# untitledfonte2.net
KiCad netlist of a schematic drawn in EAGLE
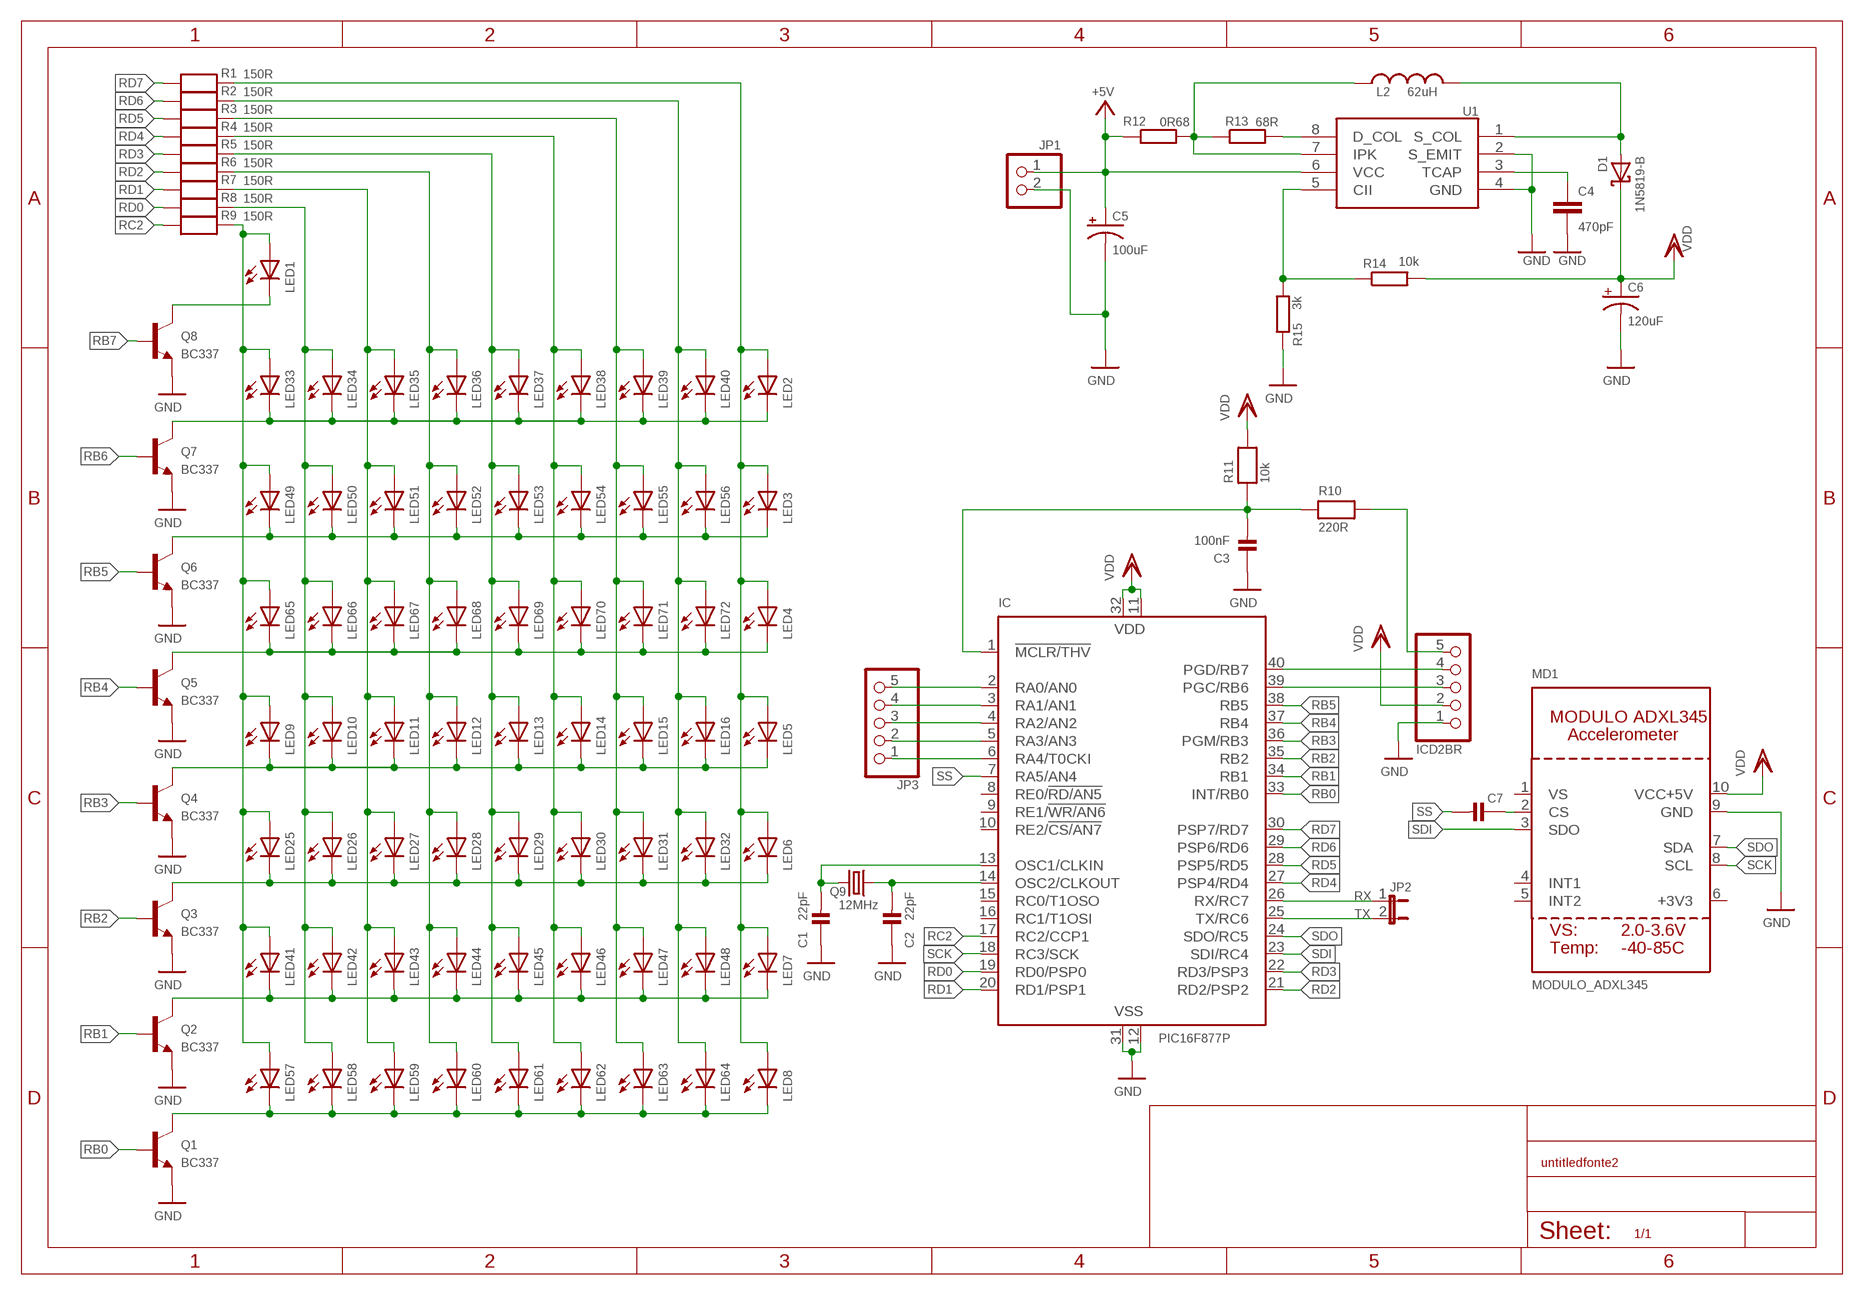
[diagram p0: schematic, sheet 1]

(export (version "E")
  (design (tool "Eeschema 10.0.6"))
  (components
    (comp (ref "C1")
      (value "22pF")
      (footprint "eagle-import:0805_NOTHERMALS")
      (libsource (lib "eagle-import") (part "CAP_CERAMIC0805-NOTHERMALS"))
    )
    (comp (ref "C2")
      (value "22pF")
      (footprint "eagle-import:0805_NOTHERMALS")
      (libsource (lib "eagle-import") (part "CAP_CERAMIC0805-NOTHERMALS"))
    )
    (comp (ref "C3")
      (value "100nF")
      (footprint "eagle-import:0805_NOTHERMALS")
      (libsource (lib "eagle-import") (part "CAP_CERAMIC0805-NOTHERMALS"))
    )
    (comp (ref "C4")
      (value "470pF")
      (footprint "eagle-import:C0805")
      (libsource (lib "eagle-import") (part "C-EUC0805"))
    )
    (comp (ref "C5")
      (value "100uF")
      (footprint "eagle-import:E2,5-5")
      (libsource (lib "eagle-import") (part "CPOL-USE2.5-5"))
    )
    (comp (ref "C6")
      (value "120uF")
      (footprint "eagle-import:E2,5-5")
      (libsource (lib "eagle-import") (part "CPOL-USE2.5-5"))
    )
    (comp (ref "C7")
      (value "CAP_CERAMIC0805-NOTHERMALS")
      (footprint "eagle-import:0805_NOTHERMALS")
      (libsource (lib "eagle-import") (part "CAP_CERAMIC0805-NOTHERMALS"))
    )
    (comp (ref "D1")
      (value "1N5819-B")
      (footprint "eagle-import:DO41-7.6")
      (libsource (lib "eagle-import") (part "1N5819-B"))
    )
    (comp (ref "IC")
      (value "PIC16F877P")
      (footprint "eagle-import:DIL40")
      (fields (field (name "MF") "MICROCHIP") (field (name "MPN") "PIC16F877-04/P"))
      (libsource (lib "eagle-import") (part "PIC16F87P7"))
    )
    (comp (ref "ICD2BR")
      (value "HEADER-1X5ROUND")
      (footprint "eagle-import:1X05_ROUND")
      (libsource (lib "eagle-import") (part "HEADER-1X5ROUND"))
    )
    (comp (ref "JP1")
      (value "HEADER-1X2")
      (footprint "eagle-import:1X02_OVAL")
      (libsource (lib "eagle-import") (part "HEADER-1X2"))
    )
    (comp (ref "JP2")
      (value "JUMPER2")
      (footprint "eagle-import:JUMPER2")
      (libsource (lib "eagle-import") (part "JUMPER2"))
    )
    (comp (ref "JP3")
      (value "HEADER-1X5ROUND")
      (footprint "eagle-import:1X05_ROUND")
      (libsource (lib "eagle-import") (part "HEADER-1X5ROUND"))
    )
    (comp (ref "L2")
      (value "62uH")
      (footprint "eagle-import:0204_5")
      (libsource (lib "eagle-import") (part "L-US0204/5"))
    )
    (comp (ref "LED1")
      (value "LED3MM")
      (footprint "eagle-import:LED3MM")
      (libsource (lib "eagle-import") (part "LED3MM"))
    )
    (comp (ref "LED2")
      (value "LED3MM")
      (footprint "eagle-import:LED3MM")
      (libsource (lib "eagle-import") (part "LED3MM"))
    )
    (comp (ref "LED3")
      (value "LED3MM")
      (footprint "eagle-import:LED3MM")
      (libsource (lib "eagle-import") (part "LED3MM"))
    )
    (comp (ref "LED4")
      (value "LED3MM")
      (footprint "eagle-import:LED3MM")
      (libsource (lib "eagle-import") (part "LED3MM"))
    )
    (comp (ref "LED5")
      (value "LED3MM")
      (footprint "eagle-import:LED3MM")
      (libsource (lib "eagle-import") (part "LED3MM"))
    )
    (comp (ref "LED6")
      (value "LED3MM")
      (footprint "eagle-import:LED3MM")
      (libsource (lib "eagle-import") (part "LED3MM"))
    )
    (comp (ref "LED7")
      (value "LED3MM")
      (footprint "eagle-import:LED3MM")
      (libsource (lib "eagle-import") (part "LED3MM"))
    )
    (comp (ref "LED8")
      (value "LED3MM")
      (footprint "eagle-import:LED3MM")
      (libsource (lib "eagle-import") (part "LED3MM"))
    )
    (comp (ref "LED9")
      (value "LED3MM")
      (footprint "eagle-import:LED3MM")
      (libsource (lib "eagle-import") (part "LED3MM"))
    )
    (comp (ref "LED10")
      (value "LED3MM")
      (footprint "eagle-import:LED3MM")
      (libsource (lib "eagle-import") (part "LED3MM"))
    )
    (comp (ref "LED11")
      (value "LED3MM")
      (footprint "eagle-import:LED3MM")
      (libsource (lib "eagle-import") (part "LED3MM"))
    )
    (comp (ref "LED12")
      (value "LED3MM")
      (footprint "eagle-import:LED3MM")
      (libsource (lib "eagle-import") (part "LED3MM"))
    )
    (comp (ref "LED13")
      (value "LED3MM")
      (footprint "eagle-import:LED3MM")
      (libsource (lib "eagle-import") (part "LED3MM"))
    )
    (comp (ref "LED14")
      (value "LED3MM")
      (footprint "eagle-import:LED3MM")
      (libsource (lib "eagle-import") (part "LED3MM"))
    )
    (comp (ref "LED15")
      (value "LED3MM")
      (footprint "eagle-import:LED3MM")
      (libsource (lib "eagle-import") (part "LED3MM"))
    )
    (comp (ref "LED16")
      (value "LED3MM")
      (footprint "eagle-import:LED3MM")
      (libsource (lib "eagle-import") (part "LED3MM"))
    )
    (comp (ref "LED25")
      (value "LED3MM")
      (footprint "eagle-import:LED3MM")
      (libsource (lib "eagle-import") (part "LED3MM"))
    )
    (comp (ref "LED26")
      (value "LED3MM")
      (footprint "eagle-import:LED3MM")
      (libsource (lib "eagle-import") (part "LED3MM"))
    )
    (comp (ref "LED27")
      (value "LED3MM")
      (footprint "eagle-import:LED3MM")
      (libsource (lib "eagle-import") (part "LED3MM"))
    )
    (comp (ref "LED28")
      (value "LED3MM")
      (footprint "eagle-import:LED3MM")
      (libsource (lib "eagle-import") (part "LED3MM"))
    )
    (comp (ref "LED29")
      (value "LED3MM")
      (footprint "eagle-import:LED3MM")
      (libsource (lib "eagle-import") (part "LED3MM"))
    )
    (comp (ref "LED30")
      (value "LED3MM")
      (footprint "eagle-import:LED3MM")
      (libsource (lib "eagle-import") (part "LED3MM"))
    )
    (comp (ref "LED31")
      (value "LED3MM")
      (footprint "eagle-import:LED3MM")
      (libsource (lib "eagle-import") (part "LED3MM"))
    )
    (comp (ref "LED32")
      (value "LED3MM")
      (footprint "eagle-import:LED3MM")
      (libsource (lib "eagle-import") (part "LED3MM"))
    )
    (comp (ref "LED33")
      (value "LED3MM")
      (footprint "eagle-import:LED3MM")
      (libsource (lib "eagle-import") (part "LED3MM"))
    )
    (comp (ref "LED34")
      (value "LED3MM")
      (footprint "eagle-import:LED3MM")
      (libsource (lib "eagle-import") (part "LED3MM"))
    )
    (comp (ref "LED35")
      (value "LED3MM")
      (footprint "eagle-import:LED3MM")
      (libsource (lib "eagle-import") (part "LED3MM"))
    )
    (comp (ref "LED36")
      (value "LED3MM")
      (footprint "eagle-import:LED3MM")
      (libsource (lib "eagle-import") (part "LED3MM"))
    )
    (comp (ref "LED37")
      (value "LED3MM")
      (footprint "eagle-import:LED3MM")
      (libsource (lib "eagle-import") (part "LED3MM"))
    )
    (comp (ref "LED38")
      (value "LED3MM")
      (footprint "eagle-import:LED3MM")
      (libsource (lib "eagle-import") (part "LED3MM"))
    )
    (comp (ref "LED39")
      (value "LED3MM")
      (footprint "eagle-import:LED3MM")
      (libsource (lib "eagle-import") (part "LED3MM"))
    )
    (comp (ref "LED40")
      (value "LED3MM")
      (footprint "eagle-import:LED3MM")
      (libsource (lib "eagle-import") (part "LED3MM"))
    )
    (comp (ref "LED41")
      (value "LED3MM")
      (footprint "eagle-import:LED3MM")
      (libsource (lib "eagle-import") (part "LED3MM"))
    )
    (comp (ref "LED42")
      (value "LED3MM")
      (footprint "eagle-import:LED3MM")
      (libsource (lib "eagle-import") (part "LED3MM"))
    )
    (comp (ref "LED43")
      (value "LED3MM")
      (footprint "eagle-import:LED3MM")
      (libsource (lib "eagle-import") (part "LED3MM"))
    )
    (comp (ref "LED44")
      (value "LED3MM")
      (footprint "eagle-import:LED3MM")
      (libsource (lib "eagle-import") (part "LED3MM"))
    )
    (comp (ref "LED45")
      (value "LED3MM")
      (footprint "eagle-import:LED3MM")
      (libsource (lib "eagle-import") (part "LED3MM"))
    )
    (comp (ref "LED46")
      (value "LED3MM")
      (footprint "eagle-import:LED3MM")
      (libsource (lib "eagle-import") (part "LED3MM"))
    )
    (comp (ref "LED47")
      (value "LED3MM")
      (footprint "eagle-import:LED3MM")
      (libsource (lib "eagle-import") (part "LED3MM"))
    )
    (comp (ref "LED48")
      (value "LED3MM")
      (footprint "eagle-import:LED3MM")
      (libsource (lib "eagle-import") (part "LED3MM"))
    )
    (comp (ref "LED49")
      (value "LED3MM")
      (footprint "eagle-import:LED3MM")
      (libsource (lib "eagle-import") (part "LED3MM"))
    )
    (comp (ref "LED50")
      (value "LED3MM")
      (footprint "eagle-import:LED3MM")
      (libsource (lib "eagle-import") (part "LED3MM"))
    )
    (comp (ref "LED51")
      (value "LED3MM")
      (footprint "eagle-import:LED3MM")
      (libsource (lib "eagle-import") (part "LED3MM"))
    )
    (comp (ref "LED52")
      (value "LED3MM")
      (footprint "eagle-import:LED3MM")
      (libsource (lib "eagle-import") (part "LED3MM"))
    )
    (comp (ref "LED53")
      (value "LED3MM")
      (footprint "eagle-import:LED3MM")
      (libsource (lib "eagle-import") (part "LED3MM"))
    )
    (comp (ref "LED54")
      (value "LED3MM")
      (footprint "eagle-import:LED3MM")
      (libsource (lib "eagle-import") (part "LED3MM"))
    )
    (comp (ref "LED55")
      (value "LED3MM")
      (footprint "eagle-import:LED3MM")
      (libsource (lib "eagle-import") (part "LED3MM"))
    )
    (comp (ref "LED56")
      (value "LED3MM")
      (footprint "eagle-import:LED3MM")
      (libsource (lib "eagle-import") (part "LED3MM"))
    )
    (comp (ref "LED57")
      (value "LED3MM")
      (footprint "eagle-import:LED3MM")
      (libsource (lib "eagle-import") (part "LED3MM"))
    )
    (comp (ref "LED58")
      (value "LED3MM")
      (footprint "eagle-import:LED3MM")
      (libsource (lib "eagle-import") (part "LED3MM"))
    )
    (comp (ref "LED59")
      (value "LED3MM")
      (footprint "eagle-import:LED3MM")
      (libsource (lib "eagle-import") (part "LED3MM"))
    )
    (comp (ref "LED60")
      (value "LED3MM")
      (footprint "eagle-import:LED3MM")
      (libsource (lib "eagle-import") (part "LED3MM"))
    )
    (comp (ref "LED61")
      (value "LED3MM")
      (footprint "eagle-import:LED3MM")
      (libsource (lib "eagle-import") (part "LED3MM"))
    )
    (comp (ref "LED62")
      (value "LED3MM")
      (footprint "eagle-import:LED3MM")
      (libsource (lib "eagle-import") (part "LED3MM"))
    )
    (comp (ref "LED63")
      (value "LED3MM")
      (footprint "eagle-import:LED3MM")
      (libsource (lib "eagle-import") (part "LED3MM"))
    )
    (comp (ref "LED64")
      (value "LED3MM")
      (footprint "eagle-import:LED3MM")
      (libsource (lib "eagle-import") (part "LED3MM"))
    )
    (comp (ref "LED65")
      (value "LED3MM")
      (footprint "eagle-import:LED3MM")
      (libsource (lib "eagle-import") (part "LED3MM"))
    )
    (comp (ref "LED66")
      (value "LED3MM")
      (footprint "eagle-import:LED3MM")
      (libsource (lib "eagle-import") (part "LED3MM"))
    )
    (comp (ref "LED67")
      (value "LED3MM")
      (footprint "eagle-import:LED3MM")
      (libsource (lib "eagle-import") (part "LED3MM"))
    )
    (comp (ref "LED68")
      (value "LED3MM")
      (footprint "eagle-import:LED3MM")
      (libsource (lib "eagle-import") (part "LED3MM"))
    )
    (comp (ref "LED69")
      (value "LED3MM")
      (footprint "eagle-import:LED3MM")
      (libsource (lib "eagle-import") (part "LED3MM"))
    )
    (comp (ref "LED70")
      (value "LED3MM")
      (footprint "eagle-import:LED3MM")
      (libsource (lib "eagle-import") (part "LED3MM"))
    )
    (comp (ref "LED71")
      (value "LED3MM")
      (footprint "eagle-import:LED3MM")
      (libsource (lib "eagle-import") (part "LED3MM"))
    )
    (comp (ref "LED72")
      (value "LED3MM")
      (footprint "eagle-import:LED3MM")
      (libsource (lib "eagle-import") (part "LED3MM"))
    )
    (comp (ref "MD1")
      (value "MODULO_ADXL345")
      (footprint "eagle-import:MODULO_ADXL345")
      (libsource (lib "eagle-import") (part "MODULO_ADXL345"))
    )
    (comp (ref "Q1")
      (value "BC337")
      (footprint "eagle-import:TO92")
      (libsource (lib "eagle-import") (part "BC337"))
    )
    (comp (ref "Q2")
      (value "BC337")
      (footprint "eagle-import:TO92")
      (libsource (lib "eagle-import") (part "BC337"))
    )
    (comp (ref "Q3")
      (value "BC337")
      (footprint "eagle-import:TO92")
      (libsource (lib "eagle-import") (part "BC337"))
    )
    (comp (ref "Q4")
      (value "BC337")
      (footprint "eagle-import:TO92")
      (libsource (lib "eagle-import") (part "BC337"))
    )
    (comp (ref "Q5")
      (value "BC337")
      (footprint "eagle-import:TO92")
      (libsource (lib "eagle-import") (part "BC337"))
    )
    (comp (ref "Q6")
      (value "BC337")
      (footprint "eagle-import:TO92")
      (libsource (lib "eagle-import") (part "BC337"))
    )
    (comp (ref "Q7")
      (value "BC337")
      (footprint "eagle-import:TO92")
      (libsource (lib "eagle-import") (part "BC337"))
    )
    (comp (ref "Q8")
      (value "BC337")
      (footprint "eagle-import:TO92")
      (libsource (lib "eagle-import") (part "BC337"))
    )
    (comp (ref "Q9")
      (value "12MHz")
      (footprint "eagle-import:HC49_S")
      (libsource (lib "eagle-import") (part "CRYSTALHC49S"))
    )
    (comp (ref "R1")
      (value "150R")
      (footprint "eagle-import:0805_NOTHERMALS")
      (libsource (lib "eagle-import") (part "RESISTOR0805_NOTHERMALS"))
    )
    (comp (ref "R2")
      (value "150R")
      (footprint "eagle-import:0805_NOTHERMALS")
      (libsource (lib "eagle-import") (part "RESISTOR0805_NOTHERMALS"))
    )
    (comp (ref "R3")
      (value "150R")
      (footprint "eagle-import:0805_NOTHERMALS")
      (libsource (lib "eagle-import") (part "RESISTOR0805_NOTHERMALS"))
    )
    (comp (ref "R4")
      (value "150R")
      (footprint "eagle-import:0805_NOTHERMALS")
      (libsource (lib "eagle-import") (part "RESISTOR0805_NOTHERMALS"))
    )
    (comp (ref "R5")
      (value "150R")
      (footprint "eagle-import:0805_NOTHERMALS")
      (libsource (lib "eagle-import") (part "RESISTOR0805_NOTHERMALS"))
    )
    (comp (ref "R6")
      (value "150R")
      (footprint "eagle-import:0805_NOTHERMALS")
      (libsource (lib "eagle-import") (part "RESISTOR0805_NOTHERMALS"))
    )
    (comp (ref "R7")
      (value "150R")
      (footprint "eagle-import:0805_NOTHERMALS")
      (libsource (lib "eagle-import") (part "RESISTOR0805_NOTHERMALS"))
    )
    (comp (ref "R8")
      (value "150R")
      (footprint "eagle-import:0805_NOTHERMALS")
      (libsource (lib "eagle-import") (part "RESISTOR0805_NOTHERMALS"))
    )
    (comp (ref "R9")
      (value "150R")
      (footprint "eagle-import:0805_NOTHERMALS")
      (libsource (lib "eagle-import") (part "RESISTOR0805_NOTHERMALS"))
    )
    (comp (ref "R10")
      (value "220R")
      (footprint "eagle-import:0805_NOTHERMALS")
      (libsource (lib "eagle-import") (part "RESISTOR0805_NOTHERMALS"))
    )
    (comp (ref "R11")
      (value "10k")
      (footprint "eagle-import:0805_NOTHERMALS")
      (libsource (lib "eagle-import") (part "RESISTOR0805_NOTHERMALS"))
    )
    (comp (ref "R12")
      (value "0R68")
      (footprint "eagle-import:0207_5V")
      (libsource (lib "eagle-import") (part "R-EU_0207/5V"))
    )
    (comp (ref "R13")
      (value "68R")
      (footprint "eagle-import:0207_2V")
      (libsource (lib "eagle-import") (part "R-EU_0207/2V"))
    )
    (comp (ref "R14")
      (value "10k")
      (footprint "eagle-import:0207_2V")
      (libsource (lib "eagle-import") (part "R-EU_0207/2V"))
    )
    (comp (ref "R15")
      (value "3k")
      (footprint "eagle-import:0207_2V")
      (libsource (lib "eagle-import") (part "R-EU_0207/2V"))
    )
    (comp (ref "U1")
      (value "MC34063A")
      (footprint "eagle-import:SOIC8_150MIL")
      (libsource (lib "eagle-import") (part "MC34063A"))
    )
  )
  (nets
    (net (code "1") (name "+5V") (class "Default")
      (node (ref "C5") (pin "+") (pinfunction "+_+") (pintype "passive"))
      (node (ref "JP1") (pin "1") (pinfunction "1_1") (pintype "passive"))
      (node (ref "R12") (pin "1") (pinfunction "1_1") (pintype "passive"))
      (node (ref "U1") (pin "6") (pinfunction "VCC_6") (pintype "bidirectional"))
    )
    (net (code "2") (name "/RX") (class "Default")
      (node (ref "IC") (pin "26") (pinfunction "RX/RC7_26") (pintype "bidirectional"))
      (node (ref "JP2") (pin "1") (pinfunction "1_1") (pintype "passive"))
    )
    (net (code "3") (name "/TX") (class "Default")
      (node (ref "IC") (pin "25") (pinfunction "TX/RC6_25") (pintype "bidirectional"))
      (node (ref "JP2") (pin "2") (pinfunction "2_2") (pintype "passive"))
    )
    (net (code "4") (name "GND") (class "Default")
      (node (ref "C1") (pin "1") (pinfunction "P$1_1") (pintype "passive"))
      (node (ref "C2") (pin "1") (pinfunction "P$1_1") (pintype "passive"))
      (node (ref "C3") (pin "1") (pinfunction "P$1_1") (pintype "passive"))
      (node (ref "C4") (pin "2") (pinfunction "2_2") (pintype "passive"))
      (node (ref "C5") (pin "-") (pinfunction "-_-") (pintype "passive"))
      (node (ref "C6") (pin "-") (pinfunction "-_-") (pintype "passive"))
      (node (ref "IC") (pin "12") (pinfunction "VSS_12") (pintype "power_in"))
      (node (ref "IC") (pin "31") (pinfunction "VSS_31") (pintype "power_in"))
      (node (ref "ICD2BR") (pin "1") (pinfunction "1_1") (pintype "passive"))
      (node (ref "JP1") (pin "2") (pinfunction "2_2") (pintype "passive"))
      (node (ref "MD1") (pin "9") (pinfunction "GND_9") (pintype "bidirectional"))
      (node (ref "Q1") (pin "1") (pinfunction "E_1") (pintype "passive"))
      (node (ref "Q2") (pin "1") (pinfunction "E_1") (pintype "passive"))
      (node (ref "Q3") (pin "1") (pinfunction "E_1") (pintype "passive"))
      (node (ref "Q4") (pin "1") (pinfunction "E_1") (pintype "passive"))
      (node (ref "Q5") (pin "1") (pinfunction "E_1") (pintype "passive"))
      (node (ref "Q6") (pin "1") (pinfunction "E_1") (pintype "passive"))
      (node (ref "Q7") (pin "1") (pinfunction "E_1") (pintype "passive"))
      (node (ref "Q8") (pin "1") (pinfunction "E_1") (pintype "passive"))
      (node (ref "R15") (pin "1") (pinfunction "1_1") (pintype "passive"))
      (node (ref "U1") (pin "2") (pinfunction "S_EMIT_2") (pintype "bidirectional"))
      (node (ref "U1") (pin "4") (pinfunction "GND_4") (pintype "bidirectional"))
    )
    (net (code "5") (name "Net-(C1-P$2)") (class "Default")
      (node (ref "C1") (pin "2") (pinfunction "P$2_2") (pintype "passive"))
      (node (ref "IC") (pin "13") (pinfunction "OSC1/CLKIN_13") (pintype "input"))
      (node (ref "Q9") (pin "2") (pinfunction "2_2") (pintype "passive"))
    )
    (net (code "6") (name "Net-(C2-P$2)") (class "Default")
      (node (ref "C2") (pin "2") (pinfunction "P$2_2") (pintype "passive"))
      (node (ref "IC") (pin "14") (pinfunction "OSC2/CLKOUT_14") (pintype "output"))
      (node (ref "Q9") (pin "1") (pinfunction "1_1") (pintype "passive"))
    )
    (net (code "7") (name "Net-(C3-P$2)") (class "Default")
      (node (ref "C3") (pin "2") (pinfunction "P$2_2") (pintype "passive"))
      (node (ref "IC") (pin "1") (pinfunction "~{MCLR/THV}_1") (pintype "input"))
      (node (ref "R10") (pin "1") (pinfunction "1_1") (pintype "passive"))
      (node (ref "R11") (pin "1") (pinfunction "1_1") (pintype "passive"))
    )
    (net (code "8") (name "Net-(C7-P$1)") (class "Default")
      (node (ref "C7") (pin "1") (pinfunction "P$1_1") (pintype "passive"))
      (node (ref "MD1") (pin "2") (pinfunction "CS_2") (pintype "bidirectional"))
    )
    (net (code "9") (name "Net-(IC-RA0{slash}AN0)") (class "Default")
      (node (ref "IC") (pin "2") (pinfunction "RA0/AN0_2") (pintype "bidirectional"))
      (node (ref "JP3") (pin "5") (pinfunction "5_5") (pintype "passive"))
    )
    (net (code "10") (name "Net-(IC-RA1{slash}AN1)") (class "Default")
      (node (ref "IC") (pin "3") (pinfunction "RA1/AN1_3") (pintype "bidirectional"))
      (node (ref "JP3") (pin "4") (pinfunction "4_4") (pintype "passive"))
    )
    (net (code "11") (name "Net-(IC-RA2{slash}AN2)") (class "Default")
      (node (ref "IC") (pin "4") (pinfunction "RA2/AN2_4") (pintype "bidirectional"))
      (node (ref "JP3") (pin "3") (pinfunction "3_3") (pintype "passive"))
    )
    (net (code "12") (name "Net-(IC-RA3{slash}AN3)") (class "Default")
      (node (ref "IC") (pin "5") (pinfunction "RA3/AN3_5") (pintype "bidirectional"))
      (node (ref "JP3") (pin "2") (pinfunction "2_2") (pintype "passive"))
    )
    (net (code "13") (name "Net-(IC-RA4{slash}T0CKI)") (class "Default")
      (node (ref "IC") (pin "6") (pinfunction "RA4/T0CKI_6") (pintype "bidirectional"))
      (node (ref "JP3") (pin "1") (pinfunction "1_1") (pintype "passive"))
    )
    (net (code "14") (name "Net-(ICD2BR-Pad5)") (class "Default")
      (node (ref "ICD2BR") (pin "5") (pinfunction "5_5") (pintype "passive"))
      (node (ref "R10") (pin "2") (pinfunction "2_2") (pintype "passive"))
    )
    (net (code "15") (name "Net-(LED1-C)") (class "Default")
      (node (ref "LED1") (pin "K") (pinfunction "C_K") (pintype "passive"))
      (node (ref "Q8") (pin "3") (pinfunction "C_3") (pintype "passive"))
    )
    (net (code "16") (name "Net-(LED1-PadA)") (class "Default")
      (node (ref "LED1") (pin "A") (pinfunction "A_A") (pintype "passive"))
      (node (ref "LED25") (pin "A") (pinfunction "A_A") (pintype "passive"))
      (node (ref "LED33") (pin "A") (pinfunction "A_A") (pintype "passive"))
      (node (ref "LED41") (pin "A") (pinfunction "A_A") (pintype "passive"))
      (node (ref "LED49") (pin "A") (pinfunction "A_A") (pintype "passive"))
      (node (ref "LED57") (pin "A") (pinfunction "A_A") (pintype "passive"))
      (node (ref "LED65") (pin "A") (pinfunction "A_A") (pintype "passive"))
      (node (ref "LED9") (pin "A") (pinfunction "A_A") (pintype "passive"))
      (node (ref "R9") (pin "2") (pinfunction "2_2") (pintype "passive"))
    )
    (net (code "17") (name "Net-(LED2-C)") (class "Default")
      (node (ref "LED2") (pin "K") (pinfunction "C_K") (pintype "passive"))
      (node (ref "LED33") (pin "K") (pinfunction "C_K") (pintype "passive"))
      (node (ref "LED34") (pin "K") (pinfunction "C_K") (pintype "passive"))
      (node (ref "LED35") (pin "K") (pinfunction "C_K") (pintype "passive"))
      (node (ref "LED36") (pin "K") (pinfunction "C_K") (pintype "passive"))
      (node (ref "LED37") (pin "K") (pinfunction "C_K") (pintype "passive"))
      (node (ref "LED38") (pin "K") (pinfunction "C_K") (pintype "passive"))
      (node (ref "LED39") (pin "K") (pinfunction "C_K") (pintype "passive"))
      (node (ref "LED40") (pin "K") (pinfunction "C_K") (pintype "passive"))
      (node (ref "Q7") (pin "3") (pinfunction "C_3") (pintype "passive"))
    )
    (net (code "18") (name "Net-(LED2-PadA)") (class "Default")
      (node (ref "LED2") (pin "A") (pinfunction "A_A") (pintype "passive"))
      (node (ref "LED3") (pin "A") (pinfunction "A_A") (pintype "passive"))
      (node (ref "LED4") (pin "A") (pinfunction "A_A") (pintype "passive"))
      (node (ref "LED5") (pin "A") (pinfunction "A_A") (pintype "passive"))
      (node (ref "LED6") (pin "A") (pinfunction "A_A") (pintype "passive"))
      (node (ref "LED7") (pin "A") (pinfunction "A_A") (pintype "passive"))
      (node (ref "LED8") (pin "A") (pinfunction "A_A") (pintype "passive"))
      (node (ref "R1") (pin "2") (pinfunction "2_2") (pintype "passive"))
    )
    (net (code "19") (name "Net-(LED3-C)") (class "Default")
      (node (ref "LED3") (pin "K") (pinfunction "C_K") (pintype "passive"))
      (node (ref "LED49") (pin "K") (pinfunction "C_K") (pintype "passive"))
      (node (ref "LED50") (pin "K") (pinfunction "C_K") (pintype "passive"))
      (node (ref "LED51") (pin "K") (pinfunction "C_K") (pintype "passive"))
      (node (ref "LED52") (pin "K") (pinfunction "C_K") (pintype "passive"))
      (node (ref "LED53") (pin "K") (pinfunction "C_K") (pintype "passive"))
      (node (ref "LED54") (pin "K") (pinfunction "C_K") (pintype "passive"))
      (node (ref "LED55") (pin "K") (pinfunction "C_K") (pintype "passive"))
      (node (ref "LED56") (pin "K") (pinfunction "C_K") (pintype "passive"))
      (node (ref "Q6") (pin "3") (pinfunction "C_3") (pintype "passive"))
    )
    (net (code "20") (name "Net-(LED4-C)") (class "Default")
      (node (ref "LED4") (pin "K") (pinfunction "C_K") (pintype "passive"))
      (node (ref "LED65") (pin "K") (pinfunction "C_K") (pintype "passive"))
      (node (ref "LED66") (pin "K") (pinfunction "C_K") (pintype "passive"))
      (node (ref "LED67") (pin "K") (pinfunction "C_K") (pintype "passive"))
      (node (ref "LED68") (pin "K") (pinfunction "C_K") (pintype "passive"))
      (node (ref "LED69") (pin "K") (pinfunction "C_K") (pintype "passive"))
      (node (ref "LED70") (pin "K") (pinfunction "C_K") (pintype "passive"))
      (node (ref "LED71") (pin "K") (pinfunction "C_K") (pintype "passive"))
      (node (ref "LED72") (pin "K") (pinfunction "C_K") (pintype "passive"))
      (node (ref "Q5") (pin "3") (pinfunction "C_3") (pintype "passive"))
    )
    (net (code "21") (name "Net-(LED10-C)") (class "Default")
      (node (ref "LED10") (pin "K") (pinfunction "C_K") (pintype "passive"))
      (node (ref "LED11") (pin "K") (pinfunction "C_K") (pintype "passive"))
      (node (ref "LED12") (pin "K") (pinfunction "C_K") (pintype "passive"))
      (node (ref "LED13") (pin "K") (pinfunction "C_K") (pintype "passive"))
      (node (ref "LED14") (pin "K") (pinfunction "C_K") (pintype "passive"))
      (node (ref "LED15") (pin "K") (pinfunction "C_K") (pintype "passive"))
      (node (ref "LED16") (pin "K") (pinfunction "C_K") (pintype "passive"))
      (node (ref "LED5") (pin "K") (pinfunction "C_K") (pintype "passive"))
      (node (ref "LED9") (pin "K") (pinfunction "C_K") (pintype "passive"))
      (node (ref "Q4") (pin "3") (pinfunction "C_3") (pintype "passive"))
    )
    (net (code "22") (name "Net-(LED10-PadA)") (class "Default")
      (node (ref "LED10") (pin "A") (pinfunction "A_A") (pintype "passive"))
      (node (ref "LED26") (pin "A") (pinfunction "A_A") (pintype "passive"))
      (node (ref "LED34") (pin "A") (pinfunction "A_A") (pintype "passive"))
      (node (ref "LED42") (pin "A") (pinfunction "A_A") (pintype "passive"))
      (node (ref "LED50") (pin "A") (pinfunction "A_A") (pintype "passive"))
      (node (ref "LED58") (pin "A") (pinfunction "A_A") (pintype "passive"))
      (node (ref "LED66") (pin "A") (pinfunction "A_A") (pintype "passive"))
      (node (ref "R8") (pin "2") (pinfunction "2_2") (pintype "passive"))
    )
    (net (code "23") (name "Net-(LED11-PadA)") (class "Default")
      (node (ref "LED11") (pin "A") (pinfunction "A_A") (pintype "passive"))
      (node (ref "LED27") (pin "A") (pinfunction "A_A") (pintype "passive"))
      (node (ref "LED35") (pin "A") (pinfunction "A_A") (pintype "passive"))
      (node (ref "LED43") (pin "A") (pinfunction "A_A") (pintype "passive"))
      (node (ref "LED51") (pin "A") (pinfunction "A_A") (pintype "passive"))
      (node (ref "LED59") (pin "A") (pinfunction "A_A") (pintype "passive"))
      (node (ref "LED67") (pin "A") (pinfunction "A_A") (pintype "passive"))
      (node (ref "R7") (pin "2") (pinfunction "2_2") (pintype "passive"))
    )
    (net (code "24") (name "Net-(LED12-PadA)") (class "Default")
      (node (ref "LED12") (pin "A") (pinfunction "A_A") (pintype "passive"))
      (node (ref "LED28") (pin "A") (pinfunction "A_A") (pintype "passive"))
      (node (ref "LED36") (pin "A") (pinfunction "A_A") (pintype "passive"))
      (node (ref "LED44") (pin "A") (pinfunction "A_A") (pintype "passive"))
      (node (ref "LED52") (pin "A") (pinfunction "A_A") (pintype "passive"))
      (node (ref "LED60") (pin "A") (pinfunction "A_A") (pintype "passive"))
      (node (ref "LED68") (pin "A") (pinfunction "A_A") (pintype "passive"))
      (node (ref "R6") (pin "2") (pinfunction "2_2") (pintype "passive"))
    )
    (net (code "25") (name "Net-(LED13-PadA)") (class "Default")
      (node (ref "LED13") (pin "A") (pinfunction "A_A") (pintype "passive"))
      (node (ref "LED29") (pin "A") (pinfunction "A_A") (pintype "passive"))
      (node (ref "LED37") (pin "A") (pinfunction "A_A") (pintype "passive"))
      (node (ref "LED45") (pin "A") (pinfunction "A_A") (pintype "passive"))
      (node (ref "LED53") (pin "A") (pinfunction "A_A") (pintype "passive"))
      (node (ref "LED61") (pin "A") (pinfunction "A_A") (pintype "passive"))
      (node (ref "LED69") (pin "A") (pinfunction "A_A") (pintype "passive"))
      (node (ref "R5") (pin "2") (pinfunction "2_2") (pintype "passive"))
    )
    (net (code "26") (name "Net-(LED14-PadA)") (class "Default")
      (node (ref "LED14") (pin "A") (pinfunction "A_A") (pintype "passive"))
      (node (ref "LED30") (pin "A") (pinfunction "A_A") (pintype "passive"))
      (node (ref "LED38") (pin "A") (pinfunction "A_A") (pintype "passive"))
      (node (ref "LED46") (pin "A") (pinfunction "A_A") (pintype "passive"))
      (node (ref "LED54") (pin "A") (pinfunction "A_A") (pintype "passive"))
      (node (ref "LED62") (pin "A") (pinfunction "A_A") (pintype "passive"))
      (node (ref "LED70") (pin "A") (pinfunction "A_A") (pintype "passive"))
      (node (ref "R4") (pin "2") (pinfunction "2_2") (pintype "passive"))
    )
    (net (code "27") (name "Net-(LED15-PadA)") (class "Default")
      (node (ref "LED15") (pin "A") (pinfunction "A_A") (pintype "passive"))
      (node (ref "LED31") (pin "A") (pinfunction "A_A") (pintype "passive"))
      (node (ref "LED39") (pin "A") (pinfunction "A_A") (pintype "passive"))
      (node (ref "LED47") (pin "A") (pinfunction "A_A") (pintype "passive"))
      (node (ref "LED55") (pin "A") (pinfunction "A_A") (pintype "passive"))
      (node (ref "LED63") (pin "A") (pinfunction "A_A") (pintype "passive"))
      (node (ref "LED71") (pin "A") (pinfunction "A_A") (pintype "passive"))
      (node (ref "R3") (pin "2") (pinfunction "2_2") (pintype "passive"))
    )
    (net (code "28") (name "Net-(LED16-PadA)") (class "Default")
      (node (ref "LED16") (pin "A") (pinfunction "A_A") (pintype "passive"))
      (node (ref "LED32") (pin "A") (pinfunction "A_A") (pintype "passive"))
      (node (ref "LED40") (pin "A") (pinfunction "A_A") (pintype "passive"))
      (node (ref "LED48") (pin "A") (pinfunction "A_A") (pintype "passive"))
      (node (ref "LED56") (pin "A") (pinfunction "A_A") (pintype "passive"))
      (node (ref "LED64") (pin "A") (pinfunction "A_A") (pintype "passive"))
      (node (ref "LED72") (pin "A") (pinfunction "A_A") (pintype "passive"))
      (node (ref "R2") (pin "2") (pinfunction "2_2") (pintype "passive"))
    )
    (net (code "29") (name "Net-(LED25-C)") (class "Default")
      (node (ref "LED25") (pin "K") (pinfunction "C_K") (pintype "passive"))
      (node (ref "LED26") (pin "K") (pinfunction "C_K") (pintype "passive"))
      (node (ref "LED27") (pin "K") (pinfunction "C_K") (pintype "passive"))
      (node (ref "LED28") (pin "K") (pinfunction "C_K") (pintype "passive"))
      (node (ref "LED29") (pin "K") (pinfunction "C_K") (pintype "passive"))
      (node (ref "LED30") (pin "K") (pinfunction "C_K") (pintype "passive"))
      (node (ref "LED31") (pin "K") (pinfunction "C_K") (pintype "passive"))
      (node (ref "LED32") (pin "K") (pinfunction "C_K") (pintype "passive"))
      (node (ref "LED6") (pin "K") (pinfunction "C_K") (pintype "passive"))
      (node (ref "Q3") (pin "3") (pinfunction "C_3") (pintype "passive"))
    )
    (net (code "30") (name "Net-(LED41-C)") (class "Default")
      (node (ref "LED41") (pin "K") (pinfunction "C_K") (pintype "passive"))
      (node (ref "LED42") (pin "K") (pinfunction "C_K") (pintype "passive"))
      (node (ref "LED43") (pin "K") (pinfunction "C_K") (pintype "passive"))
      (node (ref "LED44") (pin "K") (pinfunction "C_K") (pintype "passive"))
      (node (ref "LED45") (pin "K") (pinfunction "C_K") (pintype "passive"))
      (node (ref "LED46") (pin "K") (pinfunction "C_K") (pintype "passive"))
      (node (ref "LED47") (pin "K") (pinfunction "C_K") (pintype "passive"))
      (node (ref "LED48") (pin "K") (pinfunction "C_K") (pintype "passive"))
      (node (ref "LED7") (pin "K") (pinfunction "C_K") (pintype "passive"))
      (node (ref "Q2") (pin "3") (pinfunction "C_3") (pintype "passive"))
    )
    (net (code "31") (name "Net-(LED57-C)") (class "Default")
      (node (ref "LED57") (pin "K") (pinfunction "C_K") (pintype "passive"))
      (node (ref "LED58") (pin "K") (pinfunction "C_K") (pintype "passive"))
      (node (ref "LED59") (pin "K") (pinfunction "C_K") (pintype "passive"))
      (node (ref "LED60") (pin "K") (pinfunction "C_K") (pintype "passive"))
      (node (ref "LED61") (pin "K") (pinfunction "C_K") (pintype "passive"))
      (node (ref "LED62") (pin "K") (pinfunction "C_K") (pintype "passive"))
      (node (ref "LED63") (pin "K") (pinfunction "C_K") (pintype "passive"))
      (node (ref "LED64") (pin "K") (pinfunction "C_K") (pintype "passive"))
      (node (ref "LED8") (pin "K") (pinfunction "C_K") (pintype "passive"))
      (node (ref "Q1") (pin "3") (pinfunction "C_3") (pintype "passive"))
    )
    (net (code "32") (name "Net-(U1-CII)") (class "Default")
      (node (ref "R14") (pin "1") (pinfunction "1_1") (pintype "passive"))
      (node (ref "R15") (pin "2") (pinfunction "2_2") (pintype "passive"))
      (node (ref "U1") (pin "5") (pinfunction "CII_5") (pintype "bidirectional"))
    )
    (net (code "33") (name "Net-(U1-D_COL)") (class "Default")
      (node (ref "R13") (pin "2") (pinfunction "2_2") (pintype "passive"))
      (node (ref "U1") (pin "8") (pinfunction "D_COL_8") (pintype "bidirectional"))
    )
    (net (code "34") (name "Net-(U1-IPK)") (class "Default")
      (node (ref "L2") (pin "1") (pinfunction "1_1") (pintype "passive"))
      (node (ref "R12") (pin "2") (pinfunction "2_2") (pintype "passive"))
      (node (ref "R13") (pin "1") (pinfunction "1_1") (pintype "passive"))
      (node (ref "U1") (pin "7") (pinfunction "IPK_7") (pintype "bidirectional"))
    )
    (net (code "35") (name "Net-(U1-S_COL)") (class "Default")
      (node (ref "D1") (pin "A") (pinfunction "A_A") (pintype "passive"))
      (node (ref "L2") (pin "2") (pinfunction "2_2") (pintype "passive"))
      (node (ref "U1") (pin "1") (pinfunction "S_COL_1") (pintype "bidirectional"))
    )
    (net (code "36") (name "Net-(U1-TCAP)") (class "Default")
      (node (ref "C4") (pin "1") (pinfunction "1_1") (pintype "passive"))
      (node (ref "U1") (pin "3") (pinfunction "TCAP_3") (pintype "bidirectional"))
    )
    (net (code "37") (name "RB0") (class "Default")
      (node (ref "IC") (pin "33") (pinfunction "INT/RB0_33") (pintype "bidirectional"))
      (node (ref "Q1") (pin "2") (pinfunction "B_2") (pintype "passive"))
    )
    (net (code "38") (name "RB1") (class "Default")
      (node (ref "IC") (pin "34") (pinfunction "RB1_34") (pintype "bidirectional"))
      (node (ref "Q2") (pin "2") (pinfunction "B_2") (pintype "passive"))
    )
    (net (code "39") (name "RB2") (class "Default")
      (node (ref "IC") (pin "35") (pinfunction "RB2_35") (pintype "bidirectional"))
      (node (ref "Q3") (pin "2") (pinfunction "B_2") (pintype "passive"))
    )
    (net (code "40") (name "RB3") (class "Default")
      (node (ref "IC") (pin "36") (pinfunction "PGM/RB3_36") (pintype "bidirectional"))
      (node (ref "Q4") (pin "2") (pinfunction "B_2") (pintype "passive"))
    )
    (net (code "41") (name "RB4") (class "Default")
      (node (ref "IC") (pin "37") (pinfunction "RB4_37") (pintype "bidirectional"))
      (node (ref "Q5") (pin "2") (pinfunction "B_2") (pintype "passive"))
    )
    (net (code "42") (name "RB5") (class "Default")
      (node (ref "IC") (pin "38") (pinfunction "RB5_38") (pintype "bidirectional"))
      (node (ref "Q6") (pin "2") (pinfunction "B_2") (pintype "passive"))
    )
    (net (code "43") (name "RB6") (class "Default")
      (node (ref "IC") (pin "39") (pinfunction "PGC/RB6_39") (pintype "bidirectional"))
      (node (ref "ICD2BR") (pin "3") (pinfunction "3_3") (pintype "passive"))
      (node (ref "Q7") (pin "2") (pinfunction "B_2") (pintype "passive"))
    )
    (net (code "44") (name "RB7") (class "Default")
      (node (ref "IC") (pin "40") (pinfunction "PGD/RB7_40") (pintype "bidirectional"))
      (node (ref "ICD2BR") (pin "4") (pinfunction "4_4") (pintype "passive"))
      (node (ref "Q8") (pin "2") (pinfunction "B_2") (pintype "passive"))
    )
    (net (code "45") (name "RC2") (class "Default")
      (node (ref "IC") (pin "17") (pinfunction "RC2/CCP1_17") (pintype "bidirectional"))
      (node (ref "R9") (pin "1") (pinfunction "1_1") (pintype "passive"))
    )
    (net (code "46") (name "RD0") (class "Default")
      (node (ref "IC") (pin "19") (pinfunction "RD0/PSP0_19") (pintype "bidirectional"))
      (node (ref "R8") (pin "1") (pinfunction "1_1") (pintype "passive"))
    )
    (net (code "47") (name "RD1") (class "Default")
      (node (ref "IC") (pin "20") (pinfunction "RD1/PSP1_20") (pintype "bidirectional"))
      (node (ref "R7") (pin "1") (pinfunction "1_1") (pintype "passive"))
    )
    (net (code "48") (name "RD2") (class "Default")
      (node (ref "IC") (pin "21") (pinfunction "RD2/PSP2_21") (pintype "bidirectional"))
      (node (ref "R6") (pin "1") (pinfunction "1_1") (pintype "passive"))
    )
    (net (code "49") (name "RD3") (class "Default")
      (node (ref "IC") (pin "22") (pinfunction "RD3/PSP3_22") (pintype "bidirectional"))
      (node (ref "R5") (pin "1") (pinfunction "1_1") (pintype "passive"))
    )
    (net (code "50") (name "RD4") (class "Default")
      (node (ref "IC") (pin "27") (pinfunction "PSP4/RD4_27") (pintype "bidirectional"))
      (node (ref "R4") (pin "1") (pinfunction "1_1") (pintype "passive"))
    )
    (net (code "51") (name "RD5") (class "Default")
      (node (ref "IC") (pin "28") (pinfunction "PSP5/RD5_28") (pintype "bidirectional"))
      (node (ref "R3") (pin "1") (pinfunction "1_1") (pintype "passive"))
    )
    (net (code "52") (name "RD6") (class "Default")
      (node (ref "IC") (pin "29") (pinfunction "PSP6/RD6_29") (pintype "bidirectional"))
      (node (ref "R2") (pin "1") (pinfunction "1_1") (pintype "passive"))
    )
    (net (code "53") (name "RD7") (class "Default")
      (node (ref "IC") (pin "30") (pinfunction "PSP7/RD7_30") (pintype "bidirectional"))
      (node (ref "R1") (pin "1") (pinfunction "1_1") (pintype "passive"))
    )
    (net (code "54") (name "SCK") (class "Default")
      (node (ref "IC") (pin "18") (pinfunction "RC3/SCK_18") (pintype "bidirectional"))
      (node (ref "MD1") (pin "8") (pinfunction "SCL_8") (pintype "bidirectional"))
    )
    (net (code "55") (name "SDI") (class "Default")
      (node (ref "IC") (pin "23") (pinfunction "SDI/RC4_23") (pintype "bidirectional"))
      (node (ref "MD1") (pin "3") (pinfunction "SDO_3") (pintype "bidirectional"))
    )
    (net (code "56") (name "SDO") (class "Default")
      (node (ref "IC") (pin "24") (pinfunction "SDO/RC5_24") (pintype "bidirectional"))
      (node (ref "MD1") (pin "7") (pinfunction "SDA_7") (pintype "bidirectional"))
    )
    (net (code "57") (name "SS") (class "Default")
      (node (ref "C7") (pin "2") (pinfunction "P$2_2") (pintype "passive"))
      (node (ref "IC") (pin "7") (pinfunction "RA5/AN4_7") (pintype "bidirectional"))
    )
    (net (code "58") (name "VDD") (class "Default")
      (node (ref "C6") (pin "+") (pinfunction "+_+") (pintype "passive"))
      (node (ref "D1") (pin "C") (pinfunction "C_C") (pintype "passive"))
      (node (ref "IC") (pin "11") (pinfunction "VDD_11") (pintype "power_in"))
      (node (ref "IC") (pin "32") (pinfunction "VDD_32") (pintype "power_in"))
      (node (ref "ICD2BR") (pin "2") (pinfunction "2_2") (pintype "passive"))
      (node (ref "MD1") (pin "10") (pinfunction "VCC+5V_10") (pintype "bidirectional"))
      (node (ref "R11") (pin "2") (pinfunction "2_2") (pintype "passive"))
      (node (ref "R14") (pin "2") (pinfunction "2_2") (pintype "passive"))
    )
    (net (code "59") (name "unconnected-(IC-RC0{slash}T1OSO-Pad15)") (class "Default")
      (node (ref "IC") (pin "15") (pinfunction "RC0/T1OSO_15") (pintype "bidirectional"))
    )
    (net (code "60") (name "unconnected-(IC-RC1{slash}T1OSI-Pad16)") (class "Default")
      (node (ref "IC") (pin "16") (pinfunction "RC1/T1OSI_16") (pintype "bidirectional"))
    )
    (net (code "61") (name "unconnected-(IC-RE0{slash}~{RD{slash}AN5}-Pad8)") (class "Default")
      (node (ref "IC") (pin "8") (pinfunction "RE0/~{RD/AN5}_8") (pintype "bidirectional"))
    )
    (net (code "62") (name "unconnected-(IC-RE1{slash}~{WR{slash}AN6}-Pad9)") (class "Default")
      (node (ref "IC") (pin "9") (pinfunction "RE1/~{WR/AN6}_9") (pintype "bidirectional"))
    )
    (net (code "63") (name "unconnected-(IC-RE2{slash}~{CS{slash}AN7}-Pad10)") (class "Default")
      (node (ref "IC") (pin "10") (pinfunction "RE2/~{CS/AN7}_10") (pintype "bidirectional"))
    )
    (net (code "64") (name "unconnected-(MD1-+3V3-Pad6)") (class "Default")
      (node (ref "MD1") (pin "6") (pinfunction "+3V3_6") (pintype "bidirectional"))
    )
    (net (code "65") (name "unconnected-(MD1-INT1-Pad4)") (class "Default")
      (node (ref "MD1") (pin "4") (pinfunction "INT1_4") (pintype "bidirectional"))
    )
    (net (code "66") (name "unconnected-(MD1-INT2-Pad5)") (class "Default")
      (node (ref "MD1") (pin "5") (pinfunction "INT2_5") (pintype "bidirectional"))
    )
    (net (code "67") (name "unconnected-(MD1-VS-Pad1)") (class "Default")
      (node (ref "MD1") (pin "1") (pinfunction "VS_1") (pintype "bidirectional"))
    )
  )
)
